# DEBUG.net
KiCad netlist of a schematic drawn in Altium Designer
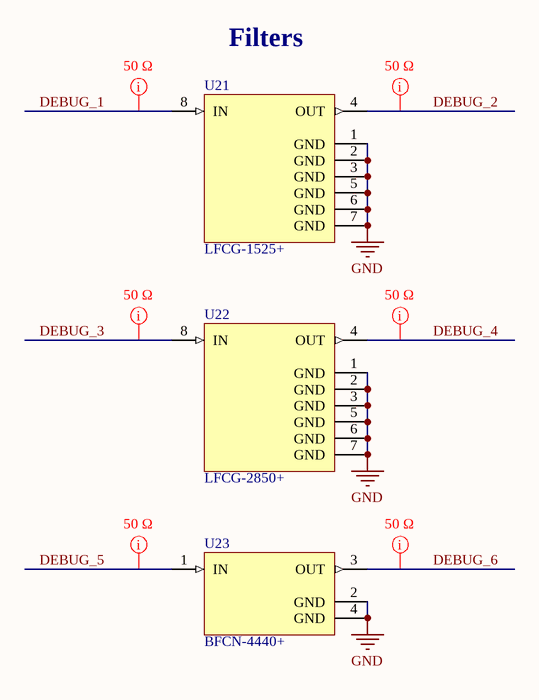
[diagram p0: DEBUG.SchDoc]

(export (version "E")
  (design (tool "Eeschema 10.0.6"))
  (components
    (comp (ref "U21")
      (value "LFCG-1525+")
      (footprint "PL-429")
      (description "Ceramic LPF, 1 Section(s) Min, 1 Section(s) Max")
      (fields (field (name "MANUFACTURER") "Mini-Circuits"))
      (libsource (lib "Titan") (part "LFCG-1525+"))
    )
    (comp (ref "U22")
      (value "LFCG-2850+")
      (footprint "PL-429")
      (description "1.8dB 50Ω 2.85GHz 0805 SMD mount 2mm*1.25mm*950μm")
      (fields (field (name "MANUFACTURER") "Mini-Circuits"))
      (libsource (lib "Titan") (part "LFCG-2850+"))
    )
    (comp (ref "U23")
      (value "BFCN-4440+")
      (footprint "FV1206")
      (description "Ceramic BPF, 1 Section(s) Min, 1 Section(s) Max, 4440MHz")
      (fields (field (name "MANUFACTURER") "Mini-Circuits"))
      (libsource (lib "Titan") (part "BFCN-4440+"))
    )
  )
  (nets
    (net (code "1") (name "/DEBUG_1") (class "Default")
      (node (ref "U21") (pin "8") (pinfunction "IN_8") (pintype "input"))
    )
    (net (code "2") (name "/DEBUG_2") (class "Default")
      (node (ref "U21") (pin "4") (pinfunction "OUT_4") (pintype "output"))
    )
    (net (code "3") (name "/DEBUG_3") (class "Default")
      (node (ref "U22") (pin "8") (pinfunction "IN_8") (pintype "input"))
    )
    (net (code "4") (name "/DEBUG_4") (class "Default")
      (node (ref "U22") (pin "4") (pinfunction "OUT_4") (pintype "output"))
    )
    (net (code "5") (name "/DEBUG_5") (class "Default")
      (node (ref "U23") (pin "1") (pinfunction "IN_1") (pintype "input"))
    )
    (net (code "6") (name "/DEBUG_6") (class "Default")
      (node (ref "U23") (pin "3") (pinfunction "OUT_3") (pintype "output"))
    )
    (net (code "7") (name "GND") (class "Default")
      (node (ref "U21") (pin "1") (pinfunction "GND_1") (pintype "power_in"))
      (node (ref "U21") (pin "2") (pinfunction "GND_2") (pintype "power_in"))
      (node (ref "U21") (pin "3") (pinfunction "GND_3") (pintype "power_in"))
      (node (ref "U21") (pin "5") (pinfunction "GND_5") (pintype "power_in"))
      (node (ref "U21") (pin "6") (pinfunction "GND_6") (pintype "power_in"))
      (node (ref "U21") (pin "7") (pinfunction "GND_7") (pintype "power_in"))
      (node (ref "U22") (pin "1") (pinfunction "GND_1") (pintype "power_in"))
      (node (ref "U22") (pin "2") (pinfunction "GND_2") (pintype "power_in"))
      (node (ref "U22") (pin "3") (pinfunction "GND_3") (pintype "power_in"))
      (node (ref "U22") (pin "5") (pinfunction "GND_5") (pintype "power_in"))
      (node (ref "U22") (pin "6") (pinfunction "GND_6") (pintype "power_in"))
      (node (ref "U22") (pin "7") (pinfunction "GND_7") (pintype "power_in"))
      (node (ref "U23") (pin "2") (pinfunction "GND_2") (pintype "power_in"))
      (node (ref "U23") (pin "4") (pinfunction "GND_4") (pintype "power_in"))
    )
  )
)
